# SPI_LVDS_Peripheral.net
KiCad netlist of a schematic drawn in Altium Designer
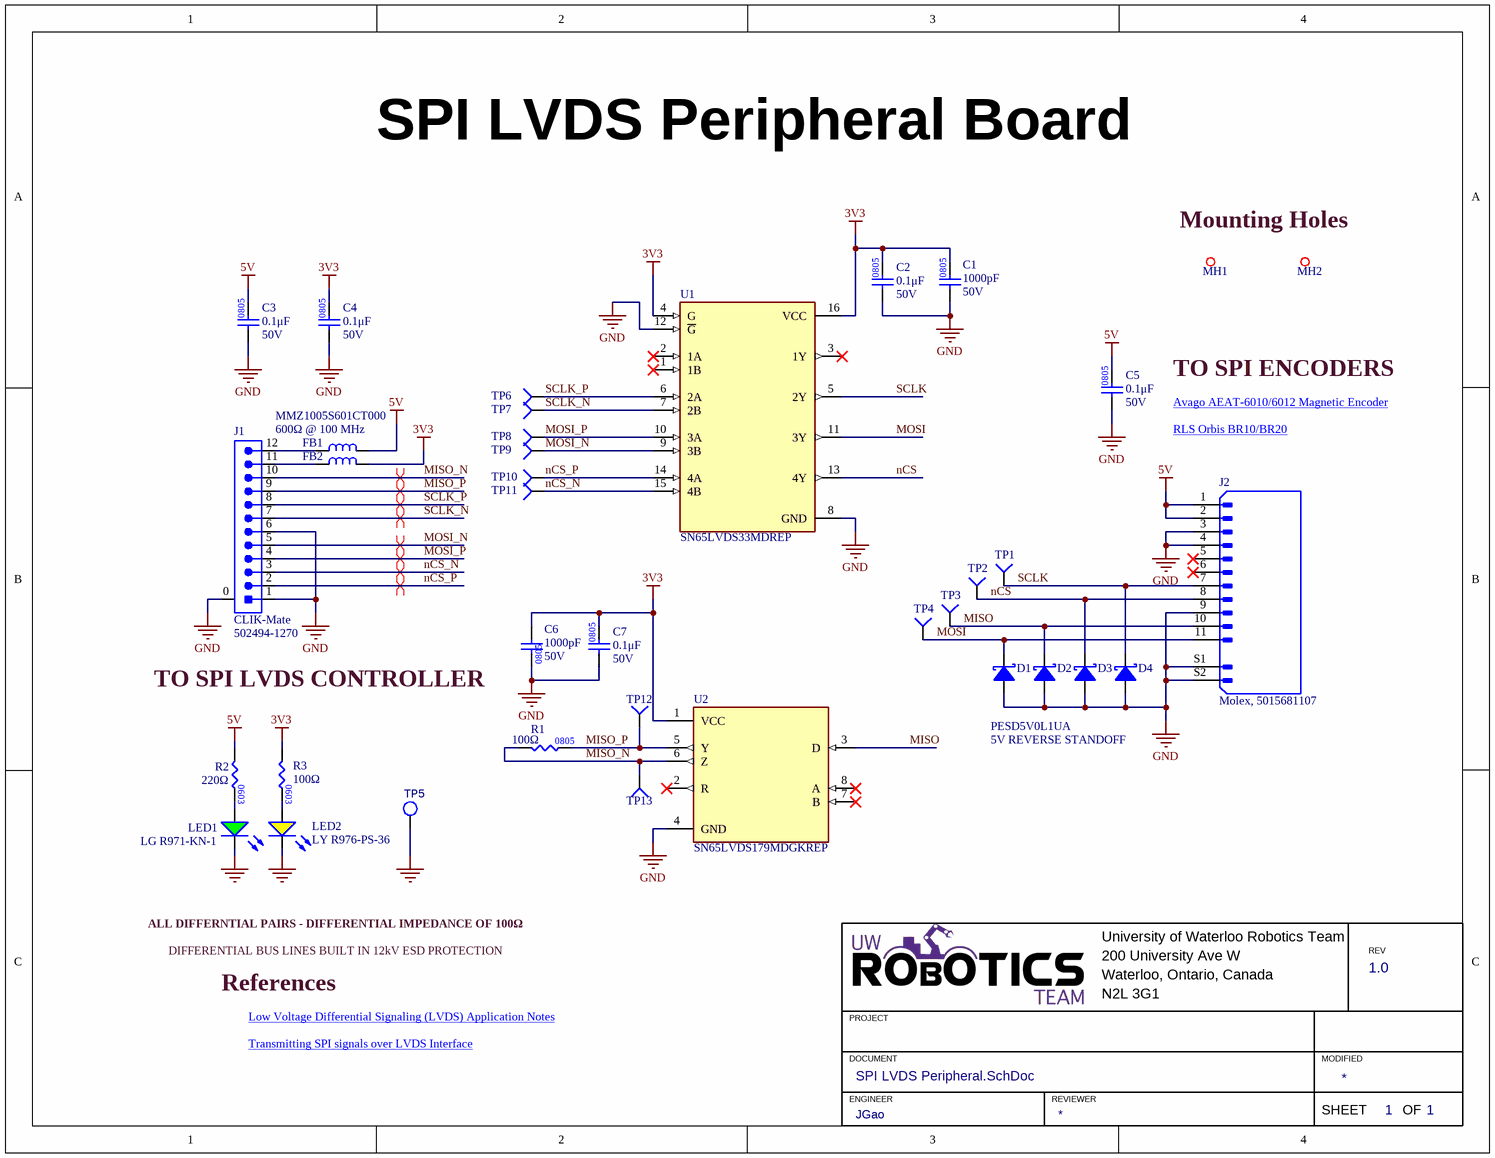
[diagram p0: SPI LVDS Peripheral.SchDoc]

(export (version "E")
  (design (tool "Eeschema 10.0.6"))
  (components
    (comp (ref "C1")
      (value "1000pF")
      (footprint "CAP2012")
      (description "CAP CER 1000pF 50V X7R 0805")
      (fields (field (name "VOLTAGE RATING") "50V") (field (name "Comment") "CAP_1000pF_50V_0805"))
      (libsource (lib "UWRT_Schematic_Library_2020") (part "CAP_1000pF_50V_0805"))
    )
    (comp (ref "C2")
      (value "0.1μF")
      (footprint "CAP2012")
      (description "CAP CER 0.1UF 50V X7R 0805")
      (fields
        (field (name "LCSC PART #") "C49678")
        (field (name "VOLTAGE RATING") "50V")
        (field (name "Comment") "CAP_0.1uF_50V_0805")
      )
      (libsource (lib "UWRT_Schematic_Library_2020") (part "CAP_0.1uF_50V_0805"))
    )
    (comp (ref "C3")
      (value "0.1μF")
      (footprint "CAP2012")
      (description "CAP CER 0.1UF 50V X7R 0805")
      (fields
        (field (name "LCSC PART #") "C49678")
        (field (name "VOLTAGE RATING") "50V")
        (field (name "Comment") "CAP_0.1uF_50V_0805")
      )
      (libsource (lib "UWRT_Schematic_Library_2020") (part "CAP_0.1uF_50V_0805"))
    )
    (comp (ref "C4")
      (value "0.1μF")
      (footprint "CAP2012")
      (description "CAP CER 0.1UF 50V X7R 0805")
      (fields
        (field (name "LCSC PART #") "C49678")
        (field (name "VOLTAGE RATING") "50V")
        (field (name "Comment") "CAP_0.1uF_50V_0805")
      )
      (libsource (lib "UWRT_Schematic_Library_2020") (part "CAP_0.1uF_50V_0805"))
    )
    (comp (ref "C5")
      (value "0.1μF")
      (footprint "CAP2012")
      (description "CAP CER 0.1UF 50V X7R 0805")
      (fields
        (field (name "LCSC PART #") "C49678")
        (field (name "VOLTAGE RATING") "50V")
        (field (name "Comment") "CAP_0.1uF_50V_0805")
      )
      (libsource (lib "UWRT_Schematic_Library_2020") (part "CAP_0.1uF_50V_0805"))
    )
    (comp (ref "C6")
      (value "1000pF")
      (footprint "CAP2012")
      (description "CAP CER 1000pF 50V X7R 0805")
      (fields (field (name "VOLTAGE RATING") "50V") (field (name "Comment") "CAP_1000pF_50V_0805"))
      (libsource (lib "UWRT_Schematic_Library_2020") (part "CAP_1000pF_50V_0805"))
    )
    (comp (ref "C7")
      (value "0.1μF")
      (footprint "CAP2012")
      (description "CAP CER 0.1UF 50V X7R 0805")
      (fields
        (field (name "LCSC PART #") "C49678")
        (field (name "VOLTAGE RATING") "50V")
        (field (name "Comment") "CAP_0.1uF_50V_0805")
      )
      (libsource (lib "UWRT_Schematic_Library_2020") (part "CAP_0.1uF_50V_0805"))
    )
    (comp (ref "D1")
      (value "TVS_DIODE_UNIDIR_5V")
      (footprint "SOD-323")
      (description "TVS DIODE 5VWM 12VC SOD-323-2")
      (fields (field (name "MANUFACTURER PART NUMBER 1") "PESD5V0L1UA"))
      (libsource (lib "UWRT_Schematic_Library_2020") (part "TVS_DIODE_UNIDIR_5V"))
    )
    (comp (ref "D2")
      (value "TVS_DIODE_UNIDIR_5V")
      (footprint "SOD-323")
      (description "TVS DIODE 5VWM 12VC SOD-323-2")
      (libsource (lib "UWRT_Schematic_Library_2020") (part "TVS_DIODE_UNIDIR_5V"))
    )
    (comp (ref "D3")
      (value "TVS_DIODE_UNIDIR_5V")
      (footprint "SOD-323")
      (description "TVS DIODE 5VWM 12VC SOD-323-2")
      (libsource (lib "UWRT_Schematic_Library_2020") (part "TVS_DIODE_UNIDIR_5V"))
    )
    (comp (ref "D4")
      (value "TVS_DIODE_UNIDIR_5V")
      (footprint "SOD-323")
      (description "TVS DIODE 5VWM 12VC SOD-323-2")
      (libsource (lib "UWRT_Schematic_Library_2020") (part "TVS_DIODE_UNIDIR_5V"))
    )
    (comp (ref "FB1")
      (value "FERRITE_BEAD_600OHM_0402")
      (footprint "RES0402")
      (description "FIXED IND 1UH 3.8A 33 MOHM SMD")
      (fields
        (field (name "MANUFACTURER PART NUMBER 1") "MMZ1005S601CT000")
        (field (name "IMPEDANCE @ FREQUENCY") "600Ω @ 100 MHz")
      )
      (libsource (lib "UWRT_Schematic_Library_2020") (part "FERRITE_BEAD_600OHM_0402"))
    )
    (comp (ref "FB2")
      (value "FERRITE_BEAD_600OHM_0402")
      (footprint "RES0402")
      (description "FIXED IND 1UH 3.8A 33 MOHM SMD")
      (libsource (lib "UWRT_Schematic_Library_2020") (part "FERRITE_BEAD_600OHM_0402"))
    )
    (comp (ref "J1")
      (value "CON_12M_SM_RA_2mm")
      (footprint "MOLEX-5024941270")
      (description "2.00mm Pitch CLIK-Mate Wire-to-Board PCB Receptacle, Single Row, Right-Angle, 12 Circuits")
      (fields
        (field (name "MANUFACTURER") "Molex")
        (field (name "MANUFACTURER PART NUMBER") "502494-1270")
        (field (name "FAMILY") "CLIK-Mate")
        (field (name "SUPPLIER PART NUMBER 1") "502494-1270")
      )
      (libsource (lib "UWRT_Schematic_Library_2020") (part "CON_12M_SM_RA_2mm"))
    )
    (comp (ref "J2")
      (value "CON_12M_SM_RA")
      (footprint "MOLEX-5015681107")
      (description "CONN HEADER SMD RIGHT ANGLE 1MM PITCH")
      (fields (field (name "MP") "Molex, 5015681107"))
      (libsource (lib "UWRT_Schematic_Library_2020") (part "CON_11M_SM_RA"))
    )
    (comp (ref "LED1")
      (value "LED_GREEN")
      (footprint "LED_0805_GREEN")
      (description "LED GREEN DIFFUSED 0805 SMD")
      (fields (field (name "MANUFACTURER PART NUMBER 1") "LG R971-KN-1"))
      (libsource (lib "UWRT_Schematic_Library_2020") (part "LED_GREEN"))
    )
    (comp (ref "LED2")
      (value "LED_YELLOW")
      (footprint "LED_0805_YELLOW")
      (description "LED YELLOW DIFFUSED 0805 SMD")
      (fields (field (name "MANUFACTURER PART NUMBER 1") "LY R976-PS-36"))
      (libsource (lib "UWRT_Schematic_Library_2020") (part "LED_YELLOW"))
    )
    (comp (ref "MH1")
      (value "MOUNTING_HOLE_M3")
      (footprint "MOUNTING_HOLE_3mm")
      (libsource (lib "UWRT_Schematic_Library_2020") (part "MOUNTING_HOLE_M3"))
    )
    (comp (ref "MH2")
      (value "MOUNTING_HOLE_M3")
      (footprint "MOUNTING_HOLE_3mm")
      (libsource (lib "UWRT_Schematic_Library_2020") (part "MOUNTING_HOLE_M3"))
    )
    (comp (ref "R1")
      (value "100Ω")
      (footprint "RES0805")
      (description "RES 100 OHM 1% 1/8W 0805")
      (fields (field (name "LCSC PART #") "C1790") (field (name "Comment") "RES_100Ω_0805_1%"))
      (libsource (lib "UWRT_Schematic_Library_2020") (part "RES_100Ω_0805_1%"))
    )
    (comp (ref "R2")
      (value "220Ω")
      (footprint "RES0603")
      (description "RES 220 OHM 5% 1/10W 0603")
      (fields (field (name "Comment") "RES_220Ω_0603_5%"))
      (libsource (lib "UWRT_Schematic_Library_2020") (part "RES_220Ω_0603_5%"))
    )
    (comp (ref "R3")
      (value "100Ω")
      (footprint "RES0603")
      (description "RES 100 OHM 1% 1/10W 0603")
      (fields (field (name "Comment") "RES_100Ω_0603_1%"))
      (libsource (lib "UWRT_Schematic_Library_2020") (part "RES_100Ω_0603_1%"))
    )
    (comp (ref "TP1")
      (value "TESTPOINT_1MM_SQUARE")
      (footprint "TESTPOINT_SQUARE_1MM")
      (description "TESTPOINT 1MM SQUARE")
      (libsource (lib "UWRT_Schematic_Library_2020") (part "TESTPOINT_1MM_SQUARE"))
    )
    (comp (ref "TP2")
      (value "TESTPOINT_1MM_SQUARE")
      (footprint "TESTPOINT_SQUARE_1MM")
      (description "TESTPOINT 1MM SQUARE")
      (libsource (lib "UWRT_Schematic_Library_2020") (part "TESTPOINT_1MM_SQUARE"))
    )
    (comp (ref "TP3")
      (value "TESTPOINT_1MM_SQUARE")
      (footprint "TESTPOINT_SQUARE_1MM")
      (description "TESTPOINT 1MM SQUARE")
      (libsource (lib "UWRT_Schematic_Library_2020") (part "TESTPOINT_1MM_SQUARE"))
    )
    (comp (ref "TP4")
      (value "TESTPOINT_1MM_SQUARE")
      (footprint "TESTPOINT_SQUARE_1MM")
      (description "TESTPOINT 1MM SQUARE")
      (libsource (lib "UWRT_Schematic_Library_2020") (part "TESTPOINT_1MM_SQUARE"))
    )
    (comp (ref "TP5")
      (value "TESTPOINT_LOOP")
      (footprint "TESTPOINT_LOOP")
      (description "TESTPOINT THRUHOLE")
      (libsource (lib "UWRT_Schematic_Library_2020") (part "TESTPOINT_LOOP"))
    )
    (comp (ref "TP6")
      (value "TESTPOINT_1MM_CIRCLE")
      (footprint "TESTPOINT_CIRCLE_1MM")
      (description "TESTPOINT 1MM CIRCLE")
      (libsource (lib "UWRT_Schematic_Library_2020") (part "TESTPOINT_1MM_CIRCLE"))
    )
    (comp (ref "TP7")
      (value "TESTPOINT_1MM_CIRCLE")
      (footprint "TESTPOINT_CIRCLE_1MM")
      (description "TESTPOINT 1MM CIRCLE")
      (libsource (lib "UWRT_Schematic_Library_2020") (part "TESTPOINT_1MM_CIRCLE"))
    )
    (comp (ref "TP8")
      (value "TESTPOINT_1MM_CIRCLE")
      (footprint "TESTPOINT_CIRCLE_1MM")
      (description "TESTPOINT 1MM CIRCLE")
      (libsource (lib "UWRT_Schematic_Library_2020") (part "TESTPOINT_1MM_CIRCLE"))
    )
    (comp (ref "TP9")
      (value "TESTPOINT_1MM_CIRCLE")
      (footprint "TESTPOINT_CIRCLE_1MM")
      (description "TESTPOINT 1MM CIRCLE")
      (libsource (lib "UWRT_Schematic_Library_2020") (part "TESTPOINT_1MM_CIRCLE"))
    )
    (comp (ref "TP10")
      (value "TESTPOINT_1MM_CIRCLE")
      (footprint "TESTPOINT_CIRCLE_1MM")
      (description "TESTPOINT 1MM CIRCLE")
      (libsource (lib "UWRT_Schematic_Library_2020") (part "TESTPOINT_1MM_CIRCLE"))
    )
    (comp (ref "TP11")
      (value "TESTPOINT_1MM_CIRCLE")
      (footprint "TESTPOINT_CIRCLE_1MM")
      (description "TESTPOINT 1MM CIRCLE")
      (libsource (lib "UWRT_Schematic_Library_2020") (part "TESTPOINT_1MM_CIRCLE"))
    )
    (comp (ref "TP12")
      (value "TESTPOINT_1MM_CIRCLE")
      (footprint "TESTPOINT_CIRCLE_1MM")
      (description "TESTPOINT 1MM CIRCLE")
      (libsource (lib "UWRT_Schematic_Library_2020") (part "TESTPOINT_1MM_CIRCLE"))
    )
    (comp (ref "TP13")
      (value "TESTPOINT_1MM_CIRCLE")
      (footprint "TESTPOINT_CIRCLE_1MM")
      (description "TESTPOINT 1MM CIRCLE")
      (libsource (lib "UWRT_Schematic_Library_2020") (part "TESTPOINT_1MM_CIRCLE"))
    )
    (comp (ref "U1")
      (value "SN65LVDS33MDREP")
      (footprint "SOIC127P600X175-16N")
      (description "IC RECEIVER 0/4 16SOIC")
      (libsource (lib "UWRT_Schematic_Library_2020") (part "SN65LVDS33MDREP"))
    )
    (comp (ref "U2")
      (value "SN65LVDS179MDGKREP")
      (footprint "SOP65P490X110-8N")
      (description "Enhanced Product High-Speed Differential Line Drivers And Receivers 8-VSSOP -55 to 125")
      (fields (field (name "MF") "Texas Instruments") (field (name "DIGI-KEY_PART_NUMBER") "296-22243-1-ND"))
      (libsource (lib "UWRT_Schematic_Library_2020") (part "SN65LVDS179MDGKREP"))
    )
  )
  (nets
    (net (code "1") (name "/MISO") (class "Default")
      (node (ref "D2") (pin "2") (pinfunction "Cathode_2") (pintype "passive"))
      (node (ref "J2") (pin "10") (pinfunction "10_10") (pintype "passive"))
      (node (ref "TP3") (pin "1") (pinfunction "=value_1") (pintype "passive"))
      (node (ref "U2") (pin "3") (pinfunction "D_3") (pintype "input"))
    )
    (net (code "2") (name "/MISO_N") (class "Default")
      (node (ref "J1") (pin "10") (pinfunction "10_10") (pintype "passive"))
      (node (ref "R1") (pin "1") (pinfunction "1_1") (pintype "passive"))
      (node (ref "TP13") (pin "1") (pinfunction "=value_1") (pintype "passive"))
      (node (ref "U2") (pin "6") (pinfunction "Z_6") (pintype "output"))
    )
    (net (code "3") (name "/MISO_P") (class "Default")
      (node (ref "J1") (pin "9") (pinfunction "9_9") (pintype "passive"))
      (node (ref "R1") (pin "2") (pinfunction "2_2") (pintype "passive"))
      (node (ref "TP12") (pin "1") (pinfunction "=value_1") (pintype "passive"))
      (node (ref "U2") (pin "5") (pinfunction "Y_5") (pintype "output"))
    )
    (net (code "4") (name "/MOSI") (class "Default")
      (node (ref "D1") (pin "2") (pinfunction "Cathode_2") (pintype "passive"))
      (node (ref "J2") (pin "11") (pinfunction "11_11") (pintype "passive"))
      (node (ref "TP4") (pin "1") (pinfunction "=value_1") (pintype "passive"))
      (node (ref "U1") (pin "11") (pinfunction "3Y_11") (pintype "output"))
    )
    (net (code "5") (name "/MOSI_N") (class "Default")
      (node (ref "J1") (pin "5") (pinfunction "5_5") (pintype "passive"))
      (node (ref "TP9") (pin "1") (pinfunction "=value_1") (pintype "passive"))
      (node (ref "U1") (pin "9") (pinfunction "3B_9") (pintype "input"))
    )
    (net (code "6") (name "/MOSI_P") (class "Default")
      (node (ref "J1") (pin "4") (pinfunction "4_4") (pintype "passive"))
      (node (ref "TP8") (pin "1") (pinfunction "=value_1") (pintype "passive"))
      (node (ref "U1") (pin "10") (pinfunction "3A_10") (pintype "input"))
    )
    (net (code "7") (name "/SCLK") (class "Default")
      (node (ref "D4") (pin "2") (pinfunction "Cathode_2") (pintype "passive"))
      (node (ref "J2") (pin "7") (pinfunction "7_7") (pintype "passive"))
      (node (ref "TP1") (pin "1") (pinfunction "=value_1") (pintype "passive"))
      (node (ref "U1") (pin "5") (pinfunction "2Y_5") (pintype "output"))
    )
    (net (code "8") (name "/SCLK_N") (class "Default")
      (node (ref "J1") (pin "7") (pinfunction "6_7") (pintype "passive"))
      (node (ref "TP7") (pin "1") (pinfunction "=value_1") (pintype "passive"))
      (node (ref "U1") (pin "7") (pinfunction "2B_7") (pintype "input"))
    )
    (net (code "9") (name "/SCLK_P") (class "Default")
      (node (ref "J1") (pin "8") (pinfunction "6_8") (pintype "passive"))
      (node (ref "TP6") (pin "1") (pinfunction "=value_1") (pintype "passive"))
      (node (ref "U1") (pin "6") (pinfunction "2A_6") (pintype "input"))
    )
    (net (code "10") (name "/nCS") (class "Default")
      (node (ref "D3") (pin "2") (pinfunction "Cathode_2") (pintype "passive"))
      (node (ref "J2") (pin "8") (pinfunction "8_8") (pintype "passive"))
      (node (ref "TP2") (pin "1") (pinfunction "=value_1") (pintype "passive"))
      (node (ref "U1") (pin "13") (pinfunction "4Y_13") (pintype "output"))
    )
    (net (code "11") (name "/nCS_N") (class "Default")
      (node (ref "J1") (pin "3") (pinfunction "3_3") (pintype "passive"))
      (node (ref "TP11") (pin "1") (pinfunction "=value_1") (pintype "passive"))
      (node (ref "U1") (pin "15") (pinfunction "4B_15") (pintype "input"))
    )
    (net (code "12") (name "/nCS_P") (class "Default")
      (node (ref "J1") (pin "2") (pinfunction "2_2") (pintype "passive"))
      (node (ref "TP10") (pin "1") (pinfunction "=value_1") (pintype "passive"))
      (node (ref "U1") (pin "14") (pinfunction "4A_14") (pintype "input"))
    )
    (net (code "13") (name "3V3") (class "Default")
      (node (ref "C1") (pin "2") (pinfunction "2_2") (pintype "passive"))
      (node (ref "C2") (pin "2") (pinfunction "2_2") (pintype "passive"))
      (node (ref "C4") (pin "2") (pinfunction "2_2") (pintype "passive"))
      (node (ref "C6") (pin "2") (pinfunction "2_2") (pintype "passive"))
      (node (ref "C7") (pin "2") (pinfunction "2_2") (pintype "passive"))
      (node (ref "FB2") (pin "1") (pinfunction "1_1") (pintype "passive"))
      (node (ref "R3") (pin "1") (pinfunction "1_1") (pintype "passive"))
      (node (ref "U1") (pin "16") (pinfunction "VCC_16") (pintype "power_in"))
      (node (ref "U1") (pin "4") (pinfunction "G_4") (pintype "input"))
      (node (ref "U2") (pin "1") (pinfunction "VCC_1") (pintype "power_in"))
    )
    (net (code "14") (name "5V") (class "Default")
      (node (ref "C3") (pin "2") (pinfunction "2_2") (pintype "passive"))
      (node (ref "C5") (pin "2") (pinfunction "2_2") (pintype "passive"))
      (node (ref "FB1") (pin "1") (pinfunction "1_1") (pintype "passive"))
      (node (ref "J2") (pin "1") (pinfunction "1_1") (pintype "passive"))
      (node (ref "J2") (pin "2") (pinfunction "2_2") (pintype "passive"))
      (node (ref "R2") (pin "1") (pinfunction "1_1") (pintype "passive"))
    )
    (net (code "15") (name "GND") (class "Default")
      (node (ref "C1") (pin "1") (pinfunction "1_1") (pintype "passive"))
      (node (ref "C2") (pin "1") (pinfunction "1_1") (pintype "passive"))
      (node (ref "C3") (pin "1") (pinfunction "1_1") (pintype "passive"))
      (node (ref "C4") (pin "1") (pinfunction "1_1") (pintype "passive"))
      (node (ref "C5") (pin "1") (pinfunction "1_1") (pintype "passive"))
      (node (ref "C6") (pin "1") (pinfunction "1_1") (pintype "passive"))
      (node (ref "C7") (pin "1") (pinfunction "1_1") (pintype "passive"))
      (node (ref "D1") (pin "1") (pinfunction "Anode_1") (pintype "passive"))
      (node (ref "D2") (pin "1") (pinfunction "Anode_1") (pintype "passive"))
      (node (ref "D3") (pin "1") (pinfunction "Anode_1") (pintype "passive"))
      (node (ref "D4") (pin "1") (pinfunction "Anode_1") (pintype "passive"))
      (node (ref "J1") (pin "0") (pinfunction "0_0") (pintype "passive"))
      (node (ref "J1") (pin "1") (pinfunction "1_1") (pintype "passive"))
      (node (ref "J1") (pin "6") (pinfunction "6_6") (pintype "passive"))
      (node (ref "J2") (pin "3") (pinfunction "3_3") (pintype "passive"))
      (node (ref "J2") (pin "4") (pinfunction "4_4") (pintype "passive"))
      (node (ref "J2") (pin "9") (pinfunction "9_9") (pintype "passive"))
      (node (ref "J2") (pin "S1") (pinfunction "SHIELD1_S1") (pintype "passive"))
      (node (ref "J2") (pin "S2") (pinfunction "SHIELD2_S2") (pintype "passive"))
      (node (ref "LED1") (pin "2") (pinfunction "K_2") (pintype "passive"))
      (node (ref "LED2") (pin "2") (pinfunction "K_2") (pintype "passive"))
      (node (ref "TP5") (pin "1") (pintype "passive"))
      (node (ref "U1") (pin "12") (pinfunction "~{G}_12") (pintype "input"))
      (node (ref "U1") (pin "8") (pinfunction "GND_8") (pintype "power_in"))
      (node (ref "U2") (pin "4") (pinfunction "GND_4") (pintype "power_in"))
    )
    (net (code "16") (name "Net-(FB1-Pad2)") (class "Default")
      (node (ref "FB1") (pin "2") (pinfunction "2_2") (pintype "passive"))
      (node (ref "J1") (pin "12") (pinfunction "12_12") (pintype "passive"))
    )
    (net (code "17") (name "Net-(FB2-Pad2)") (class "Default")
      (node (ref "FB2") (pin "2") (pinfunction "2_2") (pintype "passive"))
      (node (ref "J1") (pin "11") (pinfunction "11_11") (pintype "passive"))
    )
    (net (code "18") (name "Net-(LED1-A)") (class "Default")
      (node (ref "LED1") (pin "1") (pinfunction "A_1") (pintype "passive"))
      (node (ref "R2") (pin "2") (pinfunction "2_2") (pintype "passive"))
    )
    (net (code "19") (name "Net-(LED2-A)") (class "Default")
      (node (ref "LED2") (pin "1") (pinfunction "A_1") (pintype "passive"))
      (node (ref "R3") (pin "2") (pinfunction "2_2") (pintype "passive"))
    )
    (net (code "20") (name "unconnected-(J2-Pad5)") (class "Default")
      (node (ref "J2") (pin "5") (pinfunction "5_5") (pintype "passive+no_connect"))
    )
    (net (code "21") (name "unconnected-(J2-Pad6)") (class "Default")
      (node (ref "J2") (pin "6") (pinfunction "6_6") (pintype "passive+no_connect"))
    )
    (net (code "22") (name "unconnected-(U1-1A-Pad2)") (class "Default")
      (node (ref "U1") (pin "2") (pinfunction "1A_2") (pintype "input+no_connect"))
    )
    (net (code "23") (name "unconnected-(U1-1B-Pad1)") (class "Default")
      (node (ref "U1") (pin "1") (pinfunction "1B_1") (pintype "input+no_connect"))
    )
    (net (code "24") (name "unconnected-(U1-1Y-Pad3)") (class "Default")
      (node (ref "U1") (pin "3") (pinfunction "1Y_3") (pintype "output+no_connect"))
    )
    (net (code "25") (name "unconnected-(U2-A-Pad8)") (class "Default")
      (node (ref "U2") (pin "8") (pinfunction "A_8") (pintype "input+no_connect"))
    )
    (net (code "26") (name "unconnected-(U2-B-Pad7)") (class "Default")
      (node (ref "U2") (pin "7") (pinfunction "B_7") (pintype "input+no_connect"))
    )
    (net (code "27") (name "unconnected-(U2-R-Pad2)") (class "Default")
      (node (ref "U2") (pin "2") (pinfunction "R_2") (pintype "output+no_connect"))
    )
  )
)
